# 3_-_MOTOR-CONTROL.net
KiCad netlist of a schematic drawn in Altium Designer
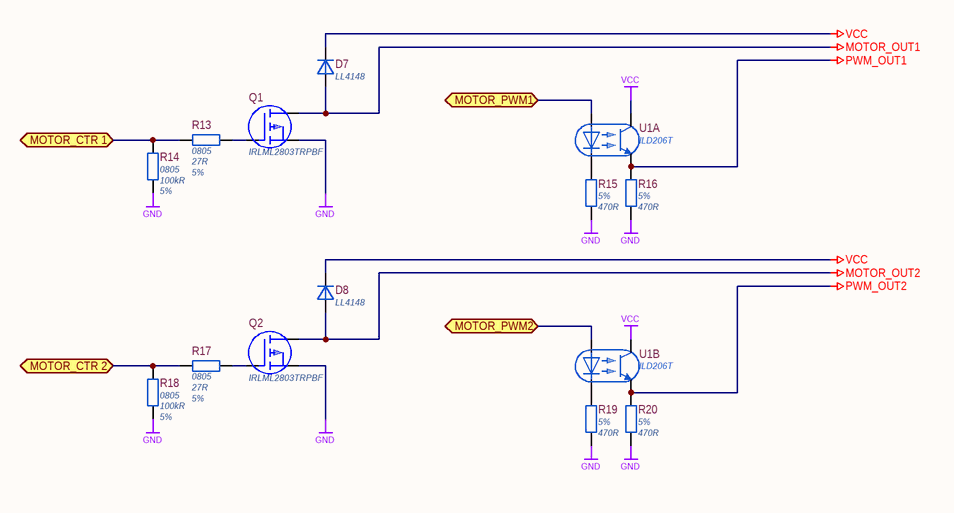
[diagram p0: [3] - MOTOR-CONTROL.SchDoc]

(export (version "E")
  (design (tool "Eeschema 10.0.6"))
  (components
    (comp (ref "D7")
      (value "LL4148")
      (footprint "SOD-89")
      (description "ON SEMICONDUCTOR - LL4148 - DIODE, SMALL SIGNAL, 100V, MINIMELF")
      (fields (field (name "VOLTAGE") "100V"))
      (libsource (lib "Diodes") (part "LL4148"))
    )
    (comp (ref "D8")
      (value "LL4148")
      (footprint "SOD-89")
      (description "ON SEMICONDUCTOR - LL4148 - DIODE, SMALL SIGNAL, 100V, MINIMELF")
      (fields (field (name "VOLTAGE") "100V"))
      (libsource (lib "Diodes") (part "LL4148"))
    )
    (comp (ref "Q1")
      (value "IRLML2803TRPBF")
      (footprint "SOT23-3")
      (description "Trans MOSFET N-CH 30V 1.2A 3-Pin SOT-23 T/R")
      (libsource (lib "Transistors") (part "IRLML2803TRPBF"))
    )
    (comp (ref "Q2")
      (value "IRLML2803TRPBF")
      (footprint "SOT23-3")
      (description "Trans MOSFET N-CH 30V 1.2A 3-Pin SOT-23 T/R")
      (libsource (lib "Transistors") (part "IRLML2803TRPBF"))
    )
    (comp (ref "R13")
      (value "RC0805JR-0727RL")
      (footprint "CH0805R")
      (description "RES SMD 27 OHM 5% 1/8W 0805")
      (fields
        (field (name "CASE CODE (IMPERIAL)") "0805")
        (field (name "RESISTANCE") "27R")
        (field (name "TOLERANCE") "5%")
      )
      (libsource (lib "Chip Resistors") (part "RC0805JR-0727RL"))
    )
    (comp (ref "R14")
      (value "RC0805JR-07100KL")
      (footprint "CH0805R")
      (description "RES SMD 100K OHM 5% 1/8W 0805")
      (fields
        (field (name "CASE CODE (IMPERIAL)") "0805")
        (field (name "RESISTANCE") "100kR")
        (field (name "TOLERANCE") "5%")
      )
      (libsource (lib "Chip Resistors") (part "RC0805JR-07100KL"))
    )
    (comp (ref "R15")
      (value "RC0805JR-07470RL")
      (footprint "CH0805R")
      (description "RES SMD 470 OHM 5% 1/8W 0805")
      (fields (field (name "TOLERANCE") "5%") (field (name "RESISTANCE") "470R"))
      (libsource (lib "Chip Resistors") (part "RC0805JR-07470RL"))
    )
    (comp (ref "R16")
      (value "RC0805JR-07470RL")
      (footprint "CH0805R")
      (description "RES SMD 470 OHM 5% 1/8W 0805")
      (fields (field (name "TOLERANCE") "5%") (field (name "RESISTANCE") "470R"))
      (libsource (lib "Chip Resistors") (part "RC0805JR-07470RL"))
    )
    (comp (ref "R17")
      (value "RC0805JR-0727RL")
      (footprint "CH0805R")
      (description "RES SMD 27 OHM 5% 1/8W 0805")
      (fields
        (field (name "CASE CODE (IMPERIAL)") "0805")
        (field (name "RESISTANCE") "27R")
        (field (name "TOLERANCE") "5%")
      )
      (libsource (lib "Chip Resistors") (part "RC0805JR-0727RL"))
    )
    (comp (ref "R18")
      (value "RC0805JR-07100KL")
      (footprint "CH0805R")
      (description "RES SMD 100K OHM 5% 1/8W 0805")
      (fields
        (field (name "CASE CODE (IMPERIAL)") "0805")
        (field (name "RESISTANCE") "100kR")
        (field (name "TOLERANCE") "5%")
      )
      (libsource (lib "Chip Resistors") (part "RC0805JR-07100KL"))
    )
    (comp (ref "R19")
      (value "RC0805JR-07470RL")
      (footprint "CH0805R")
      (description "RES SMD 470 OHM 5% 1/8W 0805")
      (fields (field (name "TOLERANCE") "5%") (field (name "RESISTANCE") "470R"))
      (libsource (lib "Chip Resistors") (part "RC0805JR-07470RL"))
    )
    (comp (ref "R20")
      (value "RC0805JR-07470RL")
      (footprint "CH0805R")
      (description "RES SMD 470 OHM 5% 1/8W 0805")
      (fields (field (name "TOLERANCE") "5%") (field (name "RESISTANCE") "470R"))
      (libsource (lib "Chip Resistors") (part "RC0805JR-07470RL"))
    )
    (comp (ref "U1")
      (value "ILD206T")
      (footprint "SOIC-8")
      (description "OPTOISOLTR 4KV 2CH TRANS 8-SOIC")
      (libsource (lib "Optoisolators") (part "ILD206T"))
    )
  )
  (nets
    (net (code "1") (name "/MOTOR_CTR 1") (class "Default")
      (node (ref "R13") (pin "1") (pinfunction "1_1") (pintype "passive"))
      (node (ref "R14") (pin "2") (pinfunction "2_2") (pintype "passive"))
    )
    (net (code "2") (name "/MOTOR_CTR 2") (class "Default")
      (node (ref "R17") (pin "1") (pinfunction "1_1") (pintype "passive"))
      (node (ref "R18") (pin "2") (pinfunction "2_2") (pintype "passive"))
    )
    (net (code "3") (name "/MOTOR_PWM1") (class "Default")
      (node (ref "U1") (pin "1") (pinfunction "A1_1") (pintype "passive"))
    )
    (net (code "4") (name "/MOTOR_PWM2") (class "Default")
      (node (ref "U1") (pin "3") (pinfunction "A2_3") (pintype "passive"))
    )
    (net (code "5") (name "GND") (class "Default")
      (node (ref "Q1") (pin "2") (pinfunction "S_2") (pintype "passive"))
      (node (ref "Q2") (pin "2") (pinfunction "S_2") (pintype "passive"))
      (node (ref "R14") (pin "1") (pinfunction "1_1") (pintype "passive"))
      (node (ref "R15") (pin "1") (pinfunction "1_1") (pintype "passive"))
      (node (ref "R16") (pin "1") (pinfunction "1_1") (pintype "passive"))
      (node (ref "R18") (pin "1") (pinfunction "1_1") (pintype "passive"))
      (node (ref "R19") (pin "1") (pinfunction "1_1") (pintype "passive"))
      (node (ref "R20") (pin "1") (pinfunction "1_1") (pintype "passive"))
    )
    (net (code "6") (name "MOTOR_OUT1") (class "Default")
      (node (ref "D7") (pin "1") (pinfunction "A_1") (pintype "passive"))
      (node (ref "Q1") (pin "3") (pinfunction "D_3") (pintype "passive"))
    )
    (net (code "7") (name "MOTOR_OUT2") (class "Default")
      (node (ref "D8") (pin "1") (pinfunction "A_1") (pintype "passive"))
      (node (ref "Q2") (pin "3") (pinfunction "D_3") (pintype "passive"))
    )
    (net (code "8") (name "Net-(Q1-G)") (class "Default")
      (node (ref "Q1") (pin "1") (pinfunction "G_1") (pintype "passive"))
      (node (ref "R13") (pin "2") (pinfunction "2_2") (pintype "passive"))
    )
    (net (code "9") (name "Net-(Q2-G)") (class "Default")
      (node (ref "Q2") (pin "1") (pinfunction "G_1") (pintype "passive"))
      (node (ref "R17") (pin "2") (pinfunction "2_2") (pintype "passive"))
    )
    (net (code "10") (name "Net-(U1A-K1)") (class "Default")
      (node (ref "R15") (pin "2") (pinfunction "2_2") (pintype "passive"))
      (node (ref "U1") (pin "2") (pinfunction "K1_2") (pintype "passive"))
    )
    (net (code "11") (name "Net-(U1B-K2)") (class "Default")
      (node (ref "R19") (pin "2") (pinfunction "2_2") (pintype "passive"))
      (node (ref "U1") (pin "4") (pinfunction "K2_4") (pintype "passive"))
    )
    (net (code "12") (name "PWM_OUT1") (class "Default")
      (node (ref "R16") (pin "2") (pinfunction "2_2") (pintype "passive"))
      (node (ref "U1") (pin "7") (pinfunction "E1_7") (pintype "passive"))
    )
    (net (code "13") (name "PWM_OUT2") (class "Default")
      (node (ref "R20") (pin "2") (pinfunction "2_2") (pintype "passive"))
      (node (ref "U1") (pin "5") (pinfunction "E2_5") (pintype "passive"))
    )
    (net (code "14") (name "VCC") (class "Default")
      (node (ref "D7") (pin "2") (pinfunction "K_2") (pintype "passive"))
      (node (ref "D8") (pin "2") (pinfunction "K_2") (pintype "passive"))
      (node (ref "U1") (pin "6") (pinfunction "C2_6") (pintype "passive"))
      (node (ref "U1") (pin "8") (pinfunction "C1_8") (pintype "passive"))
    )
  )
)
